# 03_-_TEMPLATE_SCH.net
KiCad netlist of a schematic drawn in Altium Designer
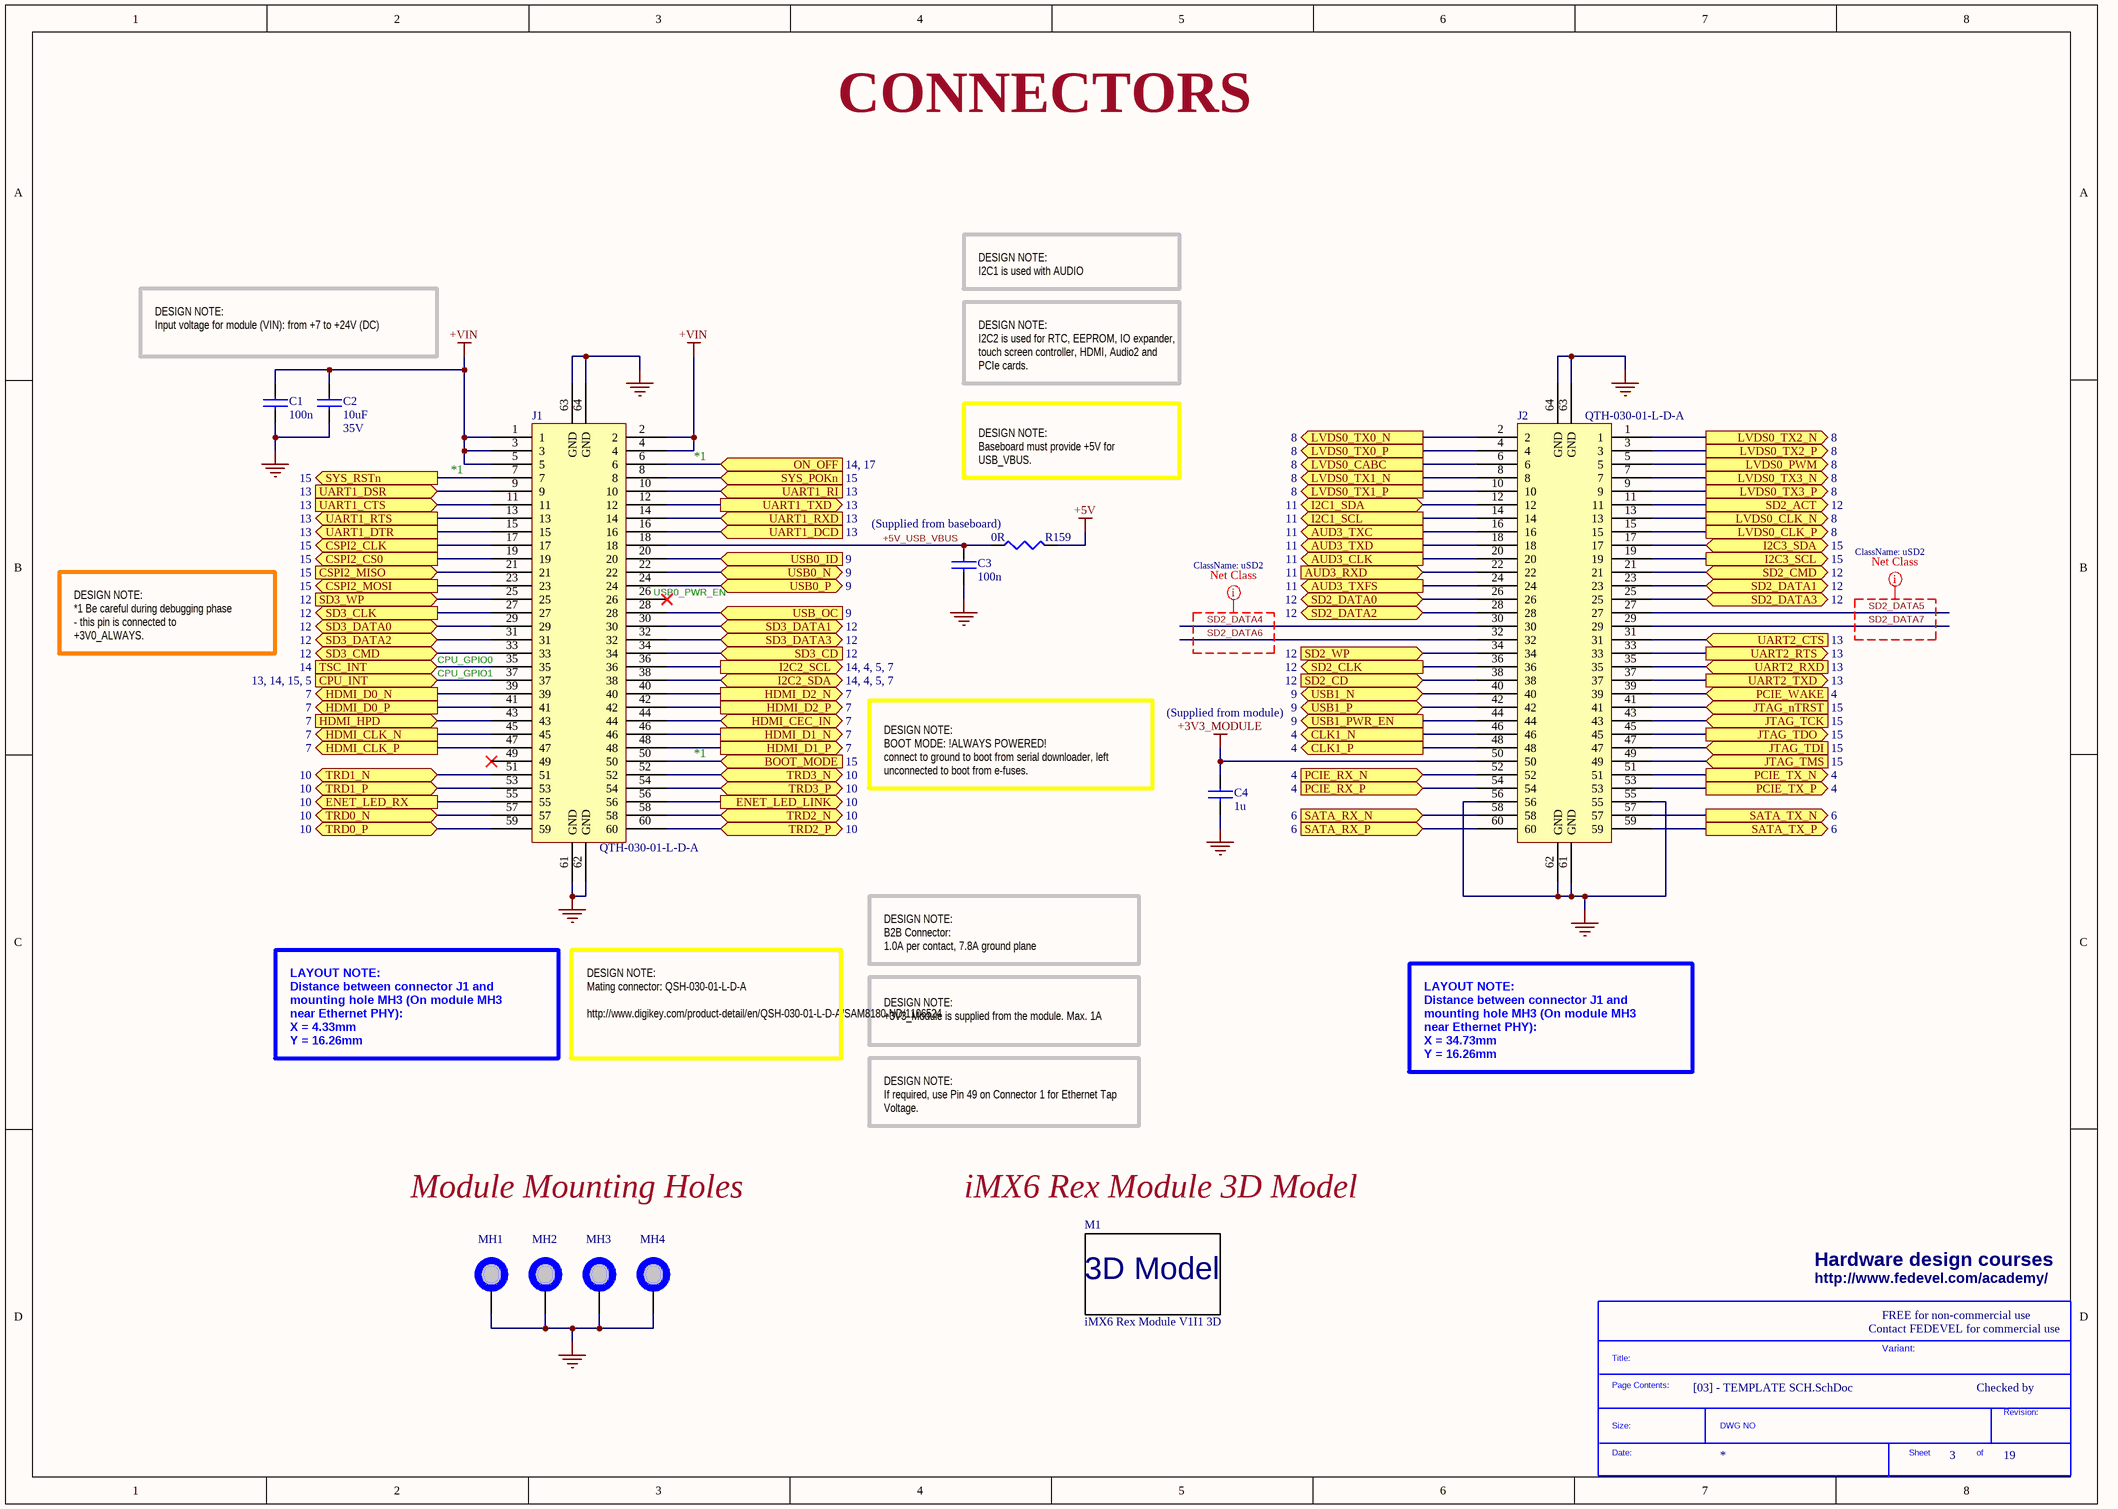
[diagram p0: [03] - TEMPLATE SCH.SchDoc]

(export (version "E")
  (design (tool "Eeschema 10.0.6"))
  (components
    (comp (ref "*") (value "SDTitleBlock") (libsource (lib "*") (part "SDTitleBlock")))
    (comp (ref "C1")
      (value "100n")
      (footprint "C0402")
      (description "CAP CER .10UF 50V X5R 10% 0402")
      (fields
        (field (name "MANUFACTURER") "TDK Corporation")
        (field (name "MANUFACTURER PART NUMBER") "C1005X5R1H104K")
      )
      (libsource (lib "Integrated_Library_RF_FEB_2012") (part "C1005X5R1H104K"))
    )
    (comp (ref "C2")
      (value "10uF")
      (footprint "C1206")
      (description "CAP CER 10UF 35V X5R 1206")
      (fields
        (field (name "MANUFACTURER") "Murata Electronics North America")
        (field (name "MANUFACTURER PART NUMBER") "GRM31CR6YA106KA12L")
        (field (name "VOLTAGE - RATED") "35V")
      )
      (libsource (lib "Integrated_Library_RF_FEB_2012") (part "GRM31CR6YA106KA12L"))
    )
    (comp (ref "C3")
      (value "100n")
      (footprint "C0402")
      (description "CAP CER .10UF 50V X5R 10% 0402")
      (fields
        (field (name "MANUFACTURER") "TDK Corporation")
        (field (name "MANUFACTURER PART NUMBER") "C1005X5R1H104K")
      )
      (libsource (lib "Integrated_Library_RF_FEB_2012") (part "C1005X5R1H104K"))
    )
    (comp (ref "C4")
      (value "1u")
      (footprint "C0402")
      (description "CAP CER 1.0UF 16V X5R 0402")
      (fields
        (field (name "MANUFACTURER") "TDK Corporation")
        (field (name "MANUFACTURER PART NUMBER") "C1005X5R1C105K")
      )
      (libsource (lib "Integrated_Library_RF_FEB_2012") (part "C1005X5R1C105K"))
    )
    (comp (ref "J1")
      (value "QTH-030-01-L-D-A")
      (footprint "QTH-030-01-L-D-A")
      (description "CONN HEADER HS .5MM 60POS DL AU")
      (fields (field (name "MANUFACTURER") "Samtec Inc"))
      (libsource (lib "Integrated_Library_RF_FEB_2012") (part "QTH-030-01-L-D-A"))
    )
    (comp (ref "J2")
      (value "QTH-030-01-L-D-A")
      (footprint "QTH-030-01-L-D-A")
      (description "CONN HEADER HS .5MM 60POS DL AU")
      (fields (field (name "MANUFACTURER") "Samtec Inc"))
      (libsource (lib "") (part "QTH-030-01-L-D-A_1"))
    )
    (comp (ref "M1")
      (value "iMX6 Rex Module V1I1 3D")
      (footprint "iMX6 Rex Module 3D")
      (description "Printed Circuit Board")
      (fields (field (name ".CREATOR") "MM"))
      (libsource (lib "Integrated_Library_RF_FEB_2012") (part "3D_iMX6_REX_MODULE_V1I1"))
    )
    (comp (ref "MH1")
      (value "MH_5MMC_2.2MMD")
      (footprint "MH_5MMD_2.2MMD")
      (description "Mounting Hole 5mm Diameter, 2.2mm Drill")
      (libsource (lib "Integrated_Library_RF_FEB_2012") (part "MH_5MMC_2.2MMD"))
    )
    (comp (ref "MH2")
      (value "MH_5MMC_2.2MMD")
      (footprint "MH_5MMD_2.2MMD")
      (description "Mounting Hole 5mm Diameter, 2.2mm Drill")
      (libsource (lib "Integrated_Library_RF_FEB_2012") (part "MH_5MMC_2.2MMD"))
    )
    (comp (ref "MH3")
      (value "MH_5MMC_2.2MMD")
      (footprint "MH_5MMD_2.2MMD")
      (description "Mounting Hole 5mm Diameter, 2.2mm Drill")
      (libsource (lib "Integrated_Library_RF_FEB_2012") (part "MH_5MMC_2.2MMD"))
    )
    (comp (ref "MH4")
      (value "MH_5MMC_2.2MMD")
      (footprint "MH_5MMD_2.2MMD")
      (description "Mounting Hole 5mm Diameter, 2.2mm Drill")
      (libsource (lib "Integrated_Library_RF_FEB_2012") (part "MH_5MMC_2.2MMD"))
    )
    (comp (ref "R159")
      (value "0R")
      (footprint "R0402")
      (description "RES 0.0 OHM 1/16W 0402 SMD")
      (fields
        (field (name "MANUFACTURER") "Yageo")
        (field (name "MANUFACTURER PART NUMBER") "RC0402JR-070RL")
      )
      (libsource (lib "Integrated_Library_RF_FEB_2012") (part "RC0402JR-070RL"))
    )
  )
  (nets
    (net (code "1") (name "+3V3_MODULE") (class "Default")
      (node (ref "C4") (pin "1") (pinfunction "1_1") (pintype "passive"))
      (node (ref "J2") (pin "50") (pinfunction "50_50") (pintype "passive"))
    )
    (net (code "2") (name "+5V") (class "Default")
      (node (ref "R159") (pin "2") (pinfunction "2_2") (pintype "passive"))
    )
    (net (code "3") (name "+VIN") (class "Default")
      (node (ref "C1") (pin "1") (pinfunction "1_1") (pintype "passive"))
      (node (ref "C2") (pin "1") (pinfunction "1_1") (pintype "passive"))
      (node (ref "J1") (pin "1") (pinfunction "1_1") (pintype "passive"))
      (node (ref "J1") (pin "2") (pinfunction "2_2") (pintype "passive"))
      (node (ref "J1") (pin "3") (pinfunction "3_3") (pintype "passive"))
      (node (ref "J1") (pin "4") (pinfunction "4_4") (pintype "passive"))
      (node (ref "J1") (pin "5") (pinfunction "5_5") (pintype "passive"))
    )
    (net (code "4") (name "/+5V_USB_VBUS") (class "Default")
      (node (ref "C3") (pin "1") (pinfunction "1_1") (pintype "passive"))
      (node (ref "J1") (pin "18") (pinfunction "18_18") (pintype "passive"))
      (node (ref "R159") (pin "1") (pinfunction "1_1") (pintype "passive"))
    )
    (net (code "5") (name "/AUD3_CLK") (class "Default")
      (node (ref "J2") (pin "20") (pinfunction "20_20") (pintype "passive"))
    )
    (net (code "6") (name "/AUD3_RXD") (class "Default")
      (node (ref "J2") (pin "22") (pinfunction "22_22") (pintype "passive"))
    )
    (net (code "7") (name "/AUD3_TXC") (class "Default")
      (node (ref "J2") (pin "16") (pinfunction "16_16") (pintype "passive"))
    )
    (net (code "8") (name "/AUD3_TXD") (class "Default")
      (node (ref "J2") (pin "18") (pinfunction "18_18") (pintype "passive"))
    )
    (net (code "9") (name "/AUD3_TXFS") (class "Default")
      (node (ref "J2") (pin "24") (pinfunction "24_24") (pintype "passive"))
    )
    (net (code "10") (name "/BOOT_MODE") (class "Default")
      (node (ref "J1") (pin "50") (pinfunction "50_50") (pintype "passive"))
    )
    (net (code "11") (name "/CLK1_N") (class "Default")
      (node (ref "J2") (pin "46") (pinfunction "46_46") (pintype "passive"))
    )
    (net (code "12") (name "/CLK1_P") (class "Default")
      (node (ref "J2") (pin "48") (pinfunction "48_48") (pintype "passive"))
    )
    (net (code "13") (name "/CPU_INT") (class "Default")
      (node (ref "J1") (pin "37") (pinfunction "37_37") (pintype "passive"))
    )
    (net (code "14") (name "/CSPI2_CLK") (class "Default")
      (node (ref "J1") (pin "17") (pinfunction "17_17") (pintype "passive"))
    )
    (net (code "15") (name "/CSPI2_CS0") (class "Default")
      (node (ref "J1") (pin "19") (pinfunction "19_19") (pintype "passive"))
    )
    (net (code "16") (name "/CSPI2_MISO") (class "Default")
      (node (ref "J1") (pin "21") (pinfunction "21_21") (pintype "passive"))
    )
    (net (code "17") (name "/CSPI2_MOSI") (class "Default")
      (node (ref "J1") (pin "23") (pinfunction "23_23") (pintype "passive"))
    )
    (net (code "18") (name "/ENET_LED_LINK") (class "Default")
      (node (ref "J1") (pin "56") (pinfunction "56_56") (pintype "passive"))
    )
    (net (code "19") (name "/ENET_LED_RX") (class "Default")
      (node (ref "J1") (pin "55") (pinfunction "55_55") (pintype "passive"))
    )
    (net (code "20") (name "/HDMI_CEC_IN") (class "Default")
      (node (ref "J1") (pin "44") (pinfunction "44_44") (pintype "passive"))
    )
    (net (code "21") (name "/HDMI_CLK_N") (class "Default")
      (node (ref "J1") (pin "45") (pinfunction "45_45") (pintype "passive"))
    )
    (net (code "22") (name "/HDMI_CLK_P") (class "Default")
      (node (ref "J1") (pin "47") (pinfunction "47_47") (pintype "passive"))
    )
    (net (code "23") (name "/HDMI_D0_N") (class "Default")
      (node (ref "J1") (pin "39") (pinfunction "39_39") (pintype "passive"))
    )
    (net (code "24") (name "/HDMI_D0_P") (class "Default")
      (node (ref "J1") (pin "41") (pinfunction "41_41") (pintype "passive"))
    )
    (net (code "25") (name "/HDMI_D1_N") (class "Default")
      (node (ref "J1") (pin "46") (pinfunction "46_46") (pintype "passive"))
    )
    (net (code "26") (name "/HDMI_D1_P") (class "Default")
      (node (ref "J1") (pin "48") (pinfunction "48_48") (pintype "passive"))
    )
    (net (code "27") (name "/HDMI_D2_N") (class "Default")
      (node (ref "J1") (pin "40") (pinfunction "40_40") (pintype "passive"))
    )
    (net (code "28") (name "/HDMI_D2_P") (class "Default")
      (node (ref "J1") (pin "42") (pinfunction "42_42") (pintype "passive"))
    )
    (net (code "29") (name "/HDMI_HPD") (class "Default")
      (node (ref "J1") (pin "43") (pinfunction "43_43") (pintype "passive"))
    )
    (net (code "30") (name "/I2C1_SCL") (class "Default")
      (node (ref "J2") (pin "14") (pinfunction "14_14") (pintype "passive"))
    )
    (net (code "31") (name "/I2C1_SDA") (class "Default")
      (node (ref "J2") (pin "12") (pinfunction "12_12") (pintype "passive"))
    )
    (net (code "32") (name "/I2C2_SCL") (class "Default")
      (node (ref "J1") (pin "36") (pinfunction "36_36") (pintype "passive"))
    )
    (net (code "33") (name "/I2C2_SDA") (class "Default")
      (node (ref "J1") (pin "38") (pinfunction "38_38") (pintype "passive"))
    )
    (net (code "34") (name "/I2C3_SCL") (class "Default")
      (node (ref "J2") (pin "19") (pinfunction "19_19") (pintype "passive"))
    )
    (net (code "35") (name "/I2C3_SDA") (class "Default")
      (node (ref "J2") (pin "17") (pinfunction "17_17") (pintype "passive"))
    )
    (net (code "36") (name "/JTAG_TCK") (class "Default")
      (node (ref "J2") (pin "43") (pinfunction "43_43") (pintype "passive"))
    )
    (net (code "37") (name "/JTAG_TDI") (class "Default")
      (node (ref "J2") (pin "47") (pinfunction "47_47") (pintype "passive"))
    )
    (net (code "38") (name "/JTAG_TDO") (class "Default")
      (node (ref "J2") (pin "45") (pinfunction "45_45") (pintype "passive"))
    )
    (net (code "39") (name "/JTAG_TMS") (class "Default")
      (node (ref "J2") (pin "49") (pinfunction "49_49") (pintype "passive"))
    )
    (net (code "40") (name "/JTAG_nTRST") (class "Default")
      (node (ref "J2") (pin "41") (pinfunction "41_41") (pintype "passive"))
    )
    (net (code "41") (name "/LVDS0_CABC") (class "Default")
      (node (ref "J2") (pin "6") (pinfunction "6_6") (pintype "passive"))
    )
    (net (code "42") (name "/LVDS0_CLK_N") (class "Default")
      (node (ref "J2") (pin "13") (pinfunction "13_13") (pintype "passive"))
    )
    (net (code "43") (name "/LVDS0_CLK_P") (class "Default")
      (node (ref "J2") (pin "15") (pinfunction "15_15") (pintype "passive"))
    )
    (net (code "44") (name "/LVDS0_PWM") (class "Default")
      (node (ref "J2") (pin "5") (pinfunction "5_5") (pintype "passive"))
    )
    (net (code "45") (name "/LVDS0_TX0_N") (class "Default")
      (node (ref "J2") (pin "2") (pinfunction "2_2") (pintype "passive"))
    )
    (net (code "46") (name "/LVDS0_TX0_P") (class "Default")
      (node (ref "J2") (pin "4") (pinfunction "4_4") (pintype "passive"))
    )
    (net (code "47") (name "/LVDS0_TX1_N") (class "Default")
      (node (ref "J2") (pin "8") (pinfunction "8_8") (pintype "passive"))
    )
    (net (code "48") (name "/LVDS0_TX1_P") (class "Default")
      (node (ref "J2") (pin "10") (pinfunction "10_10") (pintype "passive"))
    )
    (net (code "49") (name "/LVDS0_TX2_N") (class "Default")
      (node (ref "J2") (pin "1") (pinfunction "1_1") (pintype "passive"))
    )
    (net (code "50") (name "/LVDS0_TX2_P") (class "Default")
      (node (ref "J2") (pin "3") (pinfunction "3_3") (pintype "passive"))
    )
    (net (code "51") (name "/LVDS0_TX3_N") (class "Default")
      (node (ref "J2") (pin "7") (pinfunction "7_7") (pintype "passive"))
    )
    (net (code "52") (name "/LVDS0_TX3_P") (class "Default")
      (node (ref "J2") (pin "9") (pinfunction "9_9") (pintype "passive"))
    )
    (net (code "53") (name "/ON_OFF") (class "Default")
      (node (ref "J1") (pin "6") (pinfunction "6_6") (pintype "passive"))
    )
    (net (code "54") (name "/PCIE_RX_N") (class "Default")
      (node (ref "J2") (pin "52") (pinfunction "52_52") (pintype "passive"))
    )
    (net (code "55") (name "/PCIE_RX_P") (class "Default")
      (node (ref "J2") (pin "54") (pinfunction "54_54") (pintype "passive"))
    )
    (net (code "56") (name "/PCIE_TX_N") (class "Default")
      (node (ref "J2") (pin "51") (pinfunction "51_51") (pintype "passive"))
    )
    (net (code "57") (name "/PCIE_TX_P") (class "Default")
      (node (ref "J2") (pin "53") (pinfunction "53_53") (pintype "passive"))
    )
    (net (code "58") (name "/PCIE_WAKE") (class "Default")
      (node (ref "J2") (pin "39") (pinfunction "39_39") (pintype "passive"))
    )
    (net (code "59") (name "/SATA_RX_N") (class "Default")
      (node (ref "J2") (pin "58") (pinfunction "58_58") (pintype "passive"))
    )
    (net (code "60") (name "/SATA_RX_P") (class "Default")
      (node (ref "J2") (pin "60") (pinfunction "60_60") (pintype "passive"))
    )
    (net (code "61") (name "/SATA_TX_N") (class "Default")
      (node (ref "J2") (pin "57") (pinfunction "57_57") (pintype "passive"))
    )
    (net (code "62") (name "/SATA_TX_P") (class "Default")
      (node (ref "J2") (pin "59") (pinfunction "59_59") (pintype "passive"))
    )
    (net (code "63") (name "/SD2_ACT") (class "Default")
      (node (ref "J2") (pin "11") (pinfunction "11_11") (pintype "passive"))
    )
    (net (code "64") (name "/SD2_CD") (class "Default")
      (node (ref "J2") (pin "38") (pinfunction "38_38") (pintype "passive"))
    )
    (net (code "65") (name "/SD2_CLK") (class "Default")
      (node (ref "J2") (pin "36") (pinfunction "36_36") (pintype "passive"))
    )
    (net (code "66") (name "/SD2_CMD") (class "Default")
      (node (ref "J2") (pin "21") (pinfunction "21_21") (pintype "passive"))
    )
    (net (code "67") (name "/SD2_DATA0") (class "Default")
      (node (ref "J2") (pin "26") (pinfunction "26_26") (pintype "passive"))
    )
    (net (code "68") (name "/SD2_DATA1") (class "Default")
      (node (ref "J2") (pin "23") (pinfunction "23_23") (pintype "passive"))
    )
    (net (code "69") (name "/SD2_DATA2") (class "Default")
      (node (ref "J2") (pin "28") (pinfunction "28_28") (pintype "passive"))
    )
    (net (code "70") (name "/SD2_DATA3") (class "Default")
      (node (ref "J2") (pin "25") (pinfunction "25_25") (pintype "passive"))
    )
    (net (code "71") (name "/SD2_DATA4") (class "Default")
      (node (ref "J2") (pin "30") (pinfunction "30_30") (pintype "passive"))
    )
    (net (code "72") (name "/SD2_DATA5") (class "Default")
      (node (ref "J2") (pin "27") (pinfunction "27_27") (pintype "passive"))
    )
    (net (code "73") (name "/SD2_DATA6") (class "Default")
      (node (ref "J2") (pin "32") (pinfunction "32_32") (pintype "passive"))
    )
    (net (code "74") (name "/SD2_DATA7") (class "Default")
      (node (ref "J2") (pin "29") (pinfunction "29_29") (pintype "passive"))
    )
    (net (code "75") (name "/SD2_WP") (class "Default")
      (node (ref "J2") (pin "34") (pinfunction "34_34") (pintype "passive"))
    )
    (net (code "76") (name "/SD3_CD") (class "Default")
      (node (ref "J1") (pin "34") (pinfunction "34_34") (pintype "passive"))
    )
    (net (code "77") (name "/SD3_CLK") (class "Default")
      (node (ref "J1") (pin "27") (pinfunction "27_27") (pintype "passive"))
    )
    (net (code "78") (name "/SD3_CMD") (class "Default")
      (node (ref "J1") (pin "33") (pinfunction "33_33") (pintype "passive"))
    )
    (net (code "79") (name "/SD3_DATA0") (class "Default")
      (node (ref "J1") (pin "29") (pinfunction "29_29") (pintype "passive"))
    )
    (net (code "80") (name "/SD3_DATA1") (class "Default")
      (node (ref "J1") (pin "30") (pinfunction "30_30") (pintype "passive"))
    )
    (net (code "81") (name "/SD3_DATA2") (class "Default")
      (node (ref "J1") (pin "31") (pinfunction "31_31") (pintype "passive"))
    )
    (net (code "82") (name "/SD3_DATA3") (class "Default")
      (node (ref "J1") (pin "32") (pinfunction "32_32") (pintype "passive"))
    )
    (net (code "83") (name "/SD3_WP") (class "Default")
      (node (ref "J1") (pin "25") (pinfunction "25_25") (pintype "passive"))
    )
    (net (code "84") (name "/SYS_POKn") (class "Default")
      (node (ref "J1") (pin "8") (pinfunction "8_8") (pintype "passive"))
    )
    (net (code "85") (name "/SYS_RSTn") (class "Default")
      (node (ref "J1") (pin "7") (pinfunction "7_7") (pintype "passive"))
    )
    (net (code "86") (name "/TRD0_N") (class "Default")
      (node (ref "J1") (pin "57") (pinfunction "57_57") (pintype "passive"))
    )
    (net (code "87") (name "/TRD0_P") (class "Default")
      (node (ref "J1") (pin "59") (pinfunction "59_59") (pintype "passive"))
    )
    (net (code "88") (name "/TRD1_N") (class "Default")
      (node (ref "J1") (pin "51") (pinfunction "51_51") (pintype "passive"))
    )
    (net (code "89") (name "/TRD1_P") (class "Default")
      (node (ref "J1") (pin "53") (pinfunction "53_53") (pintype "passive"))
    )
    (net (code "90") (name "/TRD2_N") (class "Default")
      (node (ref "J1") (pin "58") (pinfunction "58_58") (pintype "passive"))
    )
    (net (code "91") (name "/TRD2_P") (class "Default")
      (node (ref "J1") (pin "60") (pinfunction "60_60") (pintype "passive"))
    )
    (net (code "92") (name "/TRD3_N") (class "Default")
      (node (ref "J1") (pin "52") (pinfunction "52_52") (pintype "passive"))
    )
    (net (code "93") (name "/TRD3_P") (class "Default")
      (node (ref "J1") (pin "54") (pinfunction "54_54") (pintype "passive"))
    )
    (net (code "94") (name "/TSC_INT") (class "Default")
      (node (ref "J1") (pin "35") (pinfunction "35_35") (pintype "passive"))
    )
    (net (code "95") (name "/UART1_CTS") (class "Default")
      (node (ref "J1") (pin "11") (pinfunction "11_11") (pintype "passive"))
    )
    (net (code "96") (name "/UART1_DCD") (class "Default")
      (node (ref "J1") (pin "16") (pinfunction "16_16") (pintype "passive"))
    )
    (net (code "97") (name "/UART1_DSR") (class "Default")
      (node (ref "J1") (pin "9") (pinfunction "9_9") (pintype "passive"))
    )
    (net (code "98") (name "/UART1_DTR") (class "Default")
      (node (ref "J1") (pin "15") (pinfunction "15_15") (pintype "passive"))
    )
    (net (code "99") (name "/UART1_RI") (class "Default")
      (node (ref "J1") (pin "10") (pinfunction "10_10") (pintype "passive"))
    )
    (net (code "100") (name "/UART1_RTS") (class "Default")
      (node (ref "J1") (pin "13") (pinfunction "13_13") (pintype "passive"))
    )
    (net (code "101") (name "/UART1_RXD") (class "Default")
      (node (ref "J1") (pin "14") (pinfunction "14_14") (pintype "passive"))
    )
    (net (code "102") (name "/UART1_TXD") (class "Default")
      (node (ref "J1") (pin "12") (pinfunction "12_12") (pintype "passive"))
    )
    (net (code "103") (name "/UART2_CTS") (class "Default")
      (node (ref "J2") (pin "31") (pinfunction "31_31") (pintype "passive"))
    )
    (net (code "104") (name "/UART2_RTS") (class "Default")
      (node (ref "J2") (pin "33") (pinfunction "33_33") (pintype "passive"))
    )
    (net (code "105") (name "/UART2_RXD") (class "Default")
      (node (ref "J2") (pin "35") (pinfunction "35_35") (pintype "passive"))
    )
    (net (code "106") (name "/UART2_TXD") (class "Default")
      (node (ref "J2") (pin "37") (pinfunction "37_37") (pintype "passive"))
    )
    (net (code "107") (name "/USB0_ID") (class "Default")
      (node (ref "J1") (pin "20") (pinfunction "20_20") (pintype "passive"))
    )
    (net (code "108") (name "/USB0_N") (class "Default")
      (node (ref "J1") (pin "22") (pinfunction "22_22") (pintype "passive"))
    )
    (net (code "109") (name "/USB0_P") (class "Default")
      (node (ref "J1") (pin "24") (pinfunction "24_24") (pintype "passive"))
    )
    (net (code "110") (name "/USB1_N") (class "Default")
      (node (ref "J2") (pin "40") (pinfunction "40_40") (pintype "passive"))
    )
    (net (code "111") (name "/USB1_P") (class "Default")
      (node (ref "J2") (pin "42") (pinfunction "42_42") (pintype "passive"))
    )
    (net (code "112") (name "/USB1_PWR_EN") (class "Default")
      (node (ref "J2") (pin "44") (pinfunction "44_44") (pintype "passive"))
    )
    (net (code "113") (name "/USB_OC") (class "Default")
      (node (ref "J1") (pin "28") (pinfunction "28_28") (pintype "passive"))
    )
    (net (code "114") (name "GND") (class "Default")
      (node (ref "C1") (pin "2") (pinfunction "2_2") (pintype "passive"))
      (node (ref "C2") (pin "2") (pinfunction "2_2") (pintype "passive"))
      (node (ref "C3") (pin "2") (pinfunction "2_2") (pintype "passive"))
      (node (ref "C4") (pin "2") (pinfunction "2_2") (pintype "passive"))
      (node (ref "J1") (pin "61") (pinfunction "GND_61") (pintype "passive"))
      (node (ref "J1") (pin "62") (pinfunction "GND_62") (pintype "passive"))
      (node (ref "J1") (pin "63") (pinfunction "GND_63") (pintype "passive"))
      (node (ref "J1") (pin "64") (pinfunction "GND_64") (pintype "passive"))
      (node (ref "J2") (pin "55") (pinfunction "55_55") (pintype "passive"))
      (node (ref "J2") (pin "56") (pinfunction "56_56") (pintype "passive"))
      (node (ref "J2") (pin "61") (pinfunction "GND_61") (pintype "passive"))
      (node (ref "J2") (pin "62") (pinfunction "GND_62") (pintype "passive"))
      (node (ref "J2") (pin "63") (pinfunction "GND_63") (pintype "passive"))
      (node (ref "J2") (pin "64") (pinfunction "GND_64") (pintype "passive"))
      (node (ref "MH1") (pin "1") (pinfunction "1_1") (pintype "passive"))
      (node (ref "MH2") (pin "1") (pinfunction "1_1") (pintype "passive"))
      (node (ref "MH3") (pin "1") (pinfunction "1_1") (pintype "passive"))
      (node (ref "MH4") (pin "1") (pinfunction "1_1") (pintype "passive"))
    )
    (net (code "115") (name "unconnected-(J1-HOLE1-Pad65)") (class "Default")
      (node (ref "J1") (pin "65") (pinfunction "HOLE1_65") (pintype "passive"))
    )
    (net (code "116") (name "unconnected-(J1-HOLE2-Pad66)") (class "Default")
      (node (ref "J1") (pin "66") (pinfunction "HOLE2_66") (pintype "passive"))
    )
    (net (code "117") (name "unconnected-(J1-Pad26)") (class "Default")
      (node (ref "J1") (pin "26") (pinfunction "26_26") (pintype "passive+no_connect"))
    )
    (net (code "118") (name "unconnected-(J1-Pad49)") (class "Default")
      (node (ref "J1") (pin "49") (pinfunction "49_49") (pintype "passive+no_connect"))
    )
    (net (code "119") (name "unconnected-(J2-HOLE1-Pad65)") (class "Default")
      (node (ref "J2") (pin "65") (pinfunction "HOLE1_65") (pintype "passive"))
    )
    (net (code "120") (name "unconnected-(J2-HOLE2-Pad66)") (class "Default")
      (node (ref "J2") (pin "66") (pinfunction "HOLE2_66") (pintype "passive"))
    )
  )
)
